# 8_GPS.net
KiCad netlist of a schematic drawn in Altium Designer
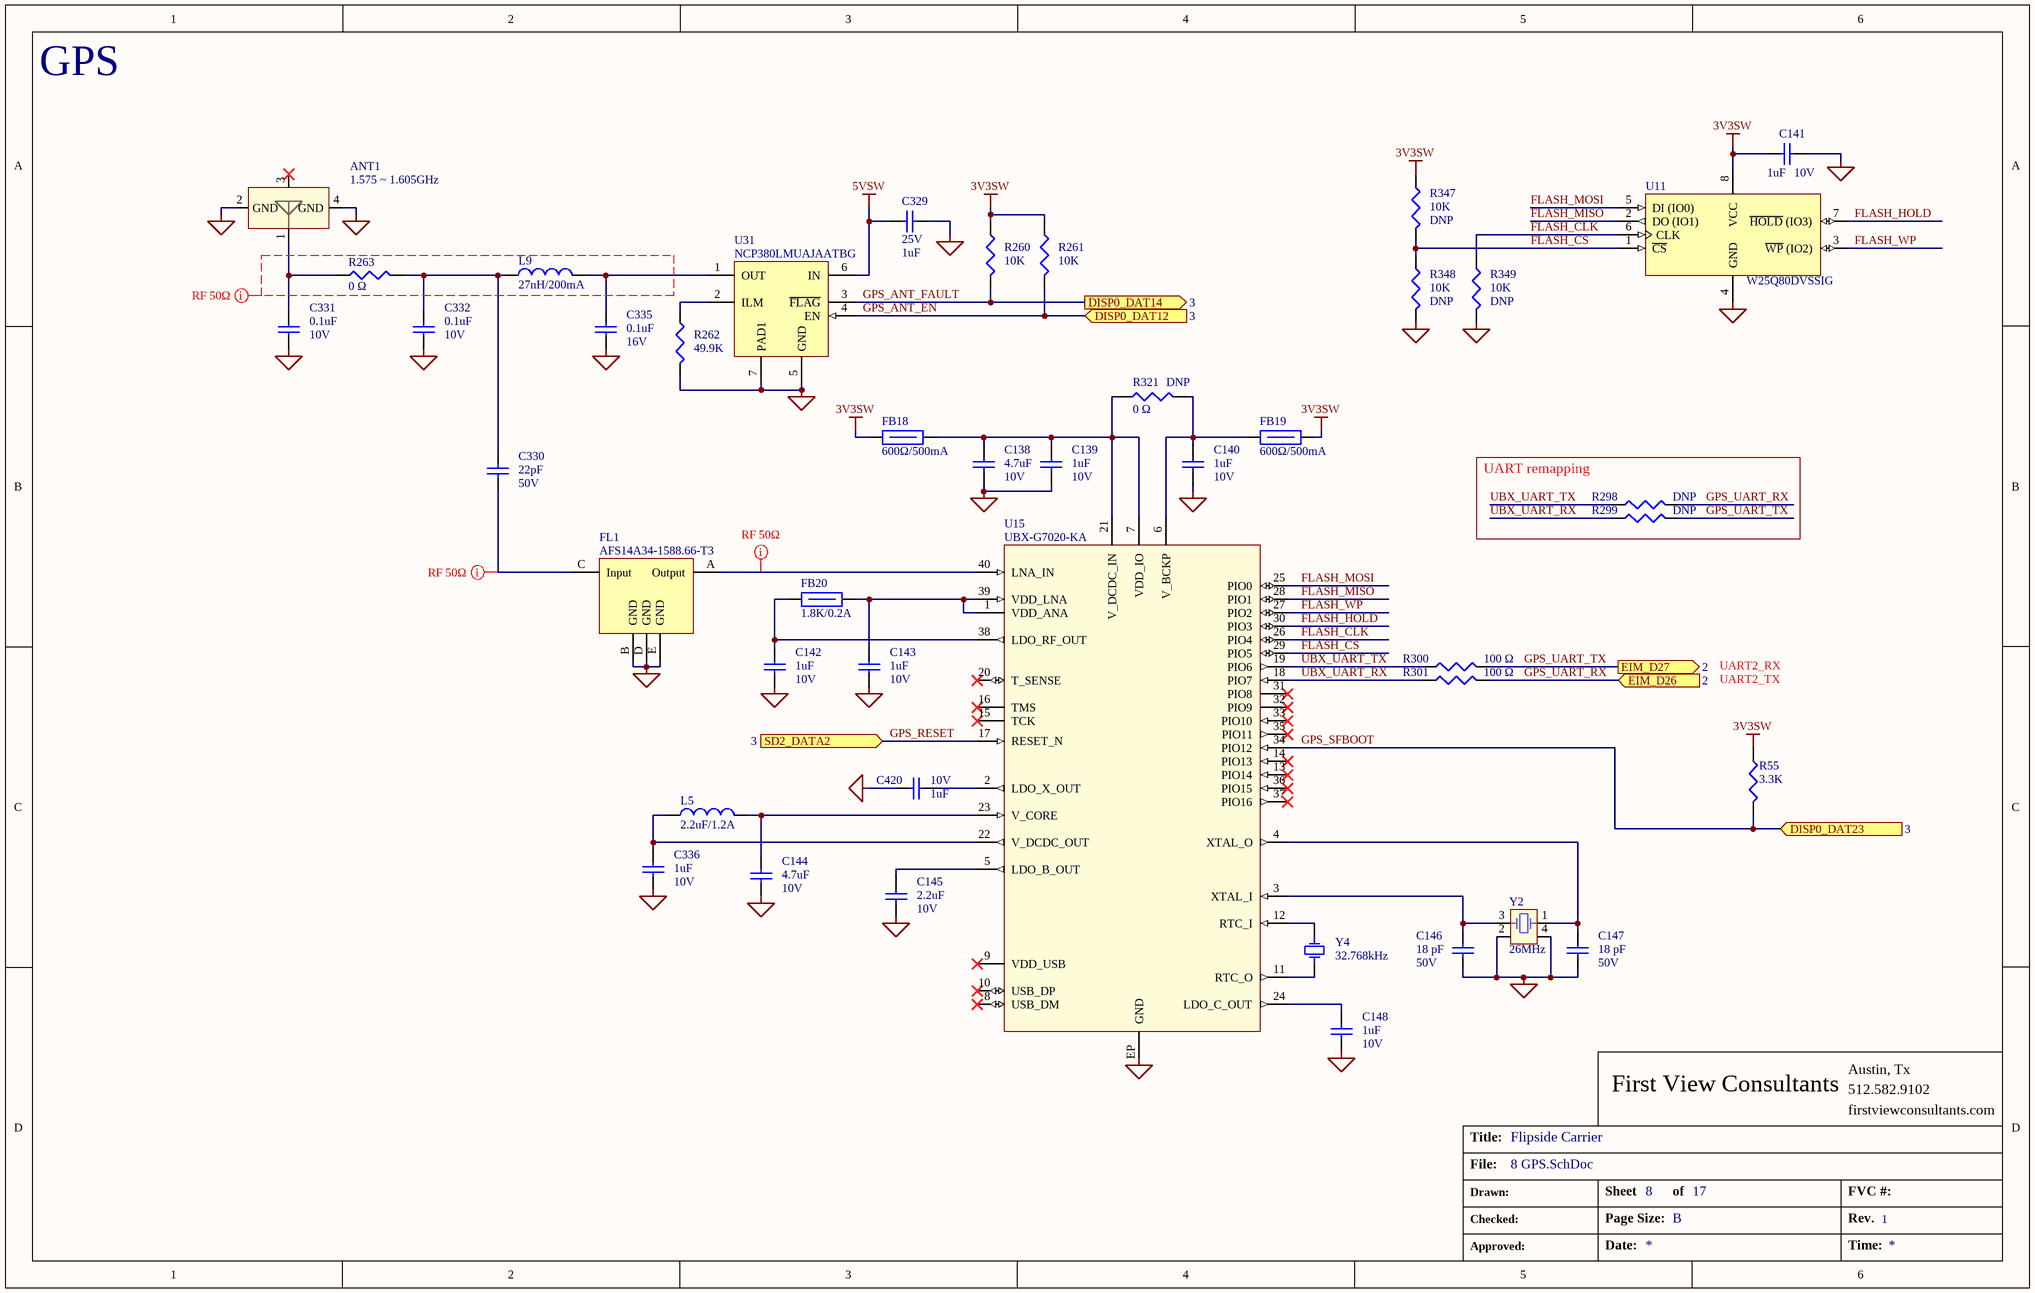
[diagram p0: 8 GPS.SchDoc]

(export (version "E")
  (design (tool "Eeschema 10.0.6"))
  (components
    (comp (ref "ANT1")
      (value "1.575 ~ 1.605GHz")
      (footprint "ANT_1575AT54A0010E")
      (description "Antenna, GPS GLONASS, SMD")
      (fields
        (field (name "MANUFACTURER") "Johanson Technology, Inc.")
        (field (name "Comment") "1575AT54A0010E")
      )
      (libsource (lib "Firstview") (part "1575AT54A0010E"))
    )
    (comp (ref "C138")
      (value "4.7uF")
      (footprint "CAP_0402")
      (description "Cap, Cer, 4.7uF, 10V, 10%, X5R, 0603")
      (fields
        (field (name "TOLERANCE") "±10%")
        (field (name "VOLTAGE") "10V")
        (field (name "MANUFACTURER") "Taiyo Yuden")
      )
      (libsource (lib "Firstview") (part "Cap 4.7uF 10V 0603"))
    )
    (comp (ref "C139")
      (value "1uF")
      (footprint "CAP_0402")
      (description "Cap, Cer, 1uF, 10V, ±10%, X5R, 0402")
      (fields
        (field (name "VOLTAGE") "10V")
        (field (name "MANUFACTURER") "Yageo")
        (field (name "Comment") "Cap 1uF 10V 0402")
      )
      (libsource (lib "Firstview") (part "Cap 1uF 10V 0402"))
    )
    (comp (ref "C140")
      (value "1uF")
      (footprint "CAP_0402")
      (description "Cap, Cer, 1uF, 10V, ±10%, X5R, 0402")
      (fields
        (field (name "VOLTAGE") "10V")
        (field (name "MANUFACTURER") "Yageo")
        (field (name "Comment") "Cap 1uF 10V 0402")
      )
      (libsource (lib "Firstview") (part "Cap 1uF 10V 0402"))
    )
    (comp (ref "C141")
      (value "1uF")
      (footprint "CAP_0402")
      (description "Cap, Cer, 1uF, 10V, ±10%, X5R, 0402")
      (fields
        (field (name "VOLTAGE") "10V")
        (field (name "MANUFACTURER") "Yageo")
        (field (name "Comment") "Cap 1uF 10V 0402")
      )
      (libsource (lib "Firstview") (part "Cap 1uF 10V 0402"))
    )
    (comp (ref "C142")
      (value "1uF")
      (footprint "CAP_0402")
      (description "Cap, Cer, 1uF, 10V, ±10%, X5R, 0402")
      (fields
        (field (name "VOLTAGE") "10V")
        (field (name "MANUFACTURER") "Yageo")
        (field (name "Comment") "Cap 1uF 10V 0402")
      )
      (libsource (lib "Firstview") (part "Cap 1uF 10V 0402"))
    )
    (comp (ref "C143")
      (value "1uF")
      (footprint "CAP_0402")
      (description "Cap, Cer, 1uF, 10V, ±10%, X5R, 0402")
      (fields
        (field (name "VOLTAGE") "10V")
        (field (name "MANUFACTURER") "Yageo")
        (field (name "Comment") "Cap 1uF 10V 0402")
      )
      (libsource (lib "Firstview") (part "Cap 1uF 10V 0402"))
    )
    (comp (ref "C144")
      (value "4.7uF")
      (footprint "CAP_0402")
      (description "Cap, Cer, 4.7uF, 10V, 10%, X5R, 0603")
      (fields
        (field (name "TOLERANCE") "±10%")
        (field (name "VOLTAGE") "10V")
        (field (name "MANUFACTURER") "Taiyo Yuden")
      )
      (libsource (lib "Firstview") (part "Cap 4.7uF 10V 0603"))
    )
    (comp (ref "C145")
      (value "2.2uF")
      (footprint "CAP_0402")
      (description "Cap, Cer, 2.2uF, 10V, 10%, X5R, 0402")
      (fields
        (field (name "VOLTAGE") "10V")
        (field (name "MANUFACTURER") "Kemet")
        (field (name "Comment") "Cap 2.2uF 10V 0402")
      )
      (libsource (lib "Firstview") (part "Cap 2.2uF 10V 0402"))
    )
    (comp (ref "C146")
      (value "18 pF")
      (footprint "CAP_0402")
      (description "Cap, Cer, 18pF, 50V, 5%, C0G, 0402")
      (fields
        (field (name "MANUFACTURER") "TDK Corporation")
        (field (name "VOLTAGE") "50V")
        (field (name "Comment") "Cap 18pF 50V 0402")
      )
      (libsource (lib "Firstview") (part "Cap 18pF 50V 0402"))
    )
    (comp (ref "C147")
      (value "18 pF")
      (footprint "CAP_0402")
      (description "Cap, Cer, 18pF, 50V, 5%, C0G, 0402")
      (fields
        (field (name "MANUFACTURER") "TDK Corporation")
        (field (name "VOLTAGE") "50V")
        (field (name "Comment") "Cap 18pF 50V 0402")
      )
      (libsource (lib "Firstview") (part "Cap 18pF 50V 0402"))
    )
    (comp (ref "C148")
      (value "1uF")
      (footprint "CAP_0402")
      (description "Cap, Cer, 1uF, 10V, ±10%, X5R, 0402")
      (fields
        (field (name "VOLTAGE") "10V")
        (field (name "MANUFACTURER") "Yageo")
        (field (name "Comment") "Cap 1uF 10V 0402")
      )
      (libsource (lib "Firstview") (part "Cap 1uF 10V 0402"))
    )
    (comp (ref "C329")
      (value "1uF")
      (footprint "CAP_0402")
      (description "Cap, Cer, 1uF, 25V, 10%, X5R, 0402")
      (fields
        (field (name "MANUFACTURER") "Taiyo Yuden")
        (field (name "VOLTAGE") "25V")
        (field (name "Comment") "Cap 1uF 25V 0402")
      )
      (libsource (lib "Firstview") (part "Cap 1uF 25V 0402"))
    )
    (comp (ref "C330")
      (value "22pF")
      (footprint "CAP_0402")
      (description "Cap, Cer, 22pF, 50V, 5%, C0G/NPO, 0402")
      (fields
        (field (name "MANUFACTURER") "Yageo")
        (field (name "VOLTAGE") "50V")
        (field (name "Comment") "Cap 22pF 50V 0402")
      )
      (libsource (lib "Firstview") (part "Cap 22pF 50V 0402"))
    )
    (comp (ref "C331")
      (value "0.1uF")
      (footprint "CAP_0402")
      (description "Cap, Cer, 0.1uF, 10V, 10%, X5R, 0402")
      (fields
        (field (name "TOLERANCE") "±10%")
        (field (name "MANUFACTURER") "Murata Electronics North America")
        (field (name "VOLTAGE") "10V")
      )
      (libsource (lib "Firstview") (part "Cap 0.1uF 10V 0402"))
    )
    (comp (ref "C332")
      (value "0.1uF")
      (footprint "CAP_0402")
      (description "Cap, Cer, 0.1uF, 10V, 10%, X5R, 0402")
      (fields
        (field (name "TOLERANCE") "±10%")
        (field (name "MANUFACTURER") "Murata Electronics North America")
        (field (name "VOLTAGE") "10V")
      )
      (libsource (lib "Firstview") (part "Cap 0.1uF 10V 0402"))
    )
    (comp (ref "C335")
      (value "0.1uF")
      (footprint "CAP_0402")
      (description "Cap, Cer, 0.1uF, 16V, 10%, X7R, 0402")
      (fields
        (field (name "TOLERANCE") "±10%")
        (field (name "MANUFACTURER") "Murata Electronics North America")
        (field (name "VOLTAGE") "16V")
      )
      (libsource (lib "Firstview") (part "Cap 0.1uF 16V 0402"))
    )
    (comp (ref "C336")
      (value "1uF")
      (footprint "CAP_0402")
      (description "Cap, Cer, 1uF, 10V, ±10%, X5R, 0402")
      (fields
        (field (name "VOLTAGE") "10V")
        (field (name "MANUFACTURER") "Yageo")
        (field (name "Comment") "Cap 1uF 10V 0402")
      )
      (libsource (lib "Firstview") (part "Cap 1uF 10V 0402"))
    )
    (comp (ref "C420")
      (value "1uF")
      (footprint "CAP_0402")
      (description "Cap, Cer, 1uF, 10V, ±10%, X5R, 0402")
      (fields
        (field (name "VOLTAGE") "10V")
        (field (name "MANUFACTURER") "Yageo")
        (field (name "Comment") "Cap 1uF 10V 0402")
      )
      (libsource (lib "Firstview") (part "Cap 1uF 10V 0402"))
    )
    (comp (ref "FB18")
      (value "600Ω/500mA")
      (footprint "IND_0603")
      (description "Ind, Ferrite Bead, 600R, 350mOhm, 0.5A, 0603")
      (fields
        (field (name "MANUFACTURER") "Murata Electronics North America")
        (field (name "Comment") "BLM18EG601SN1D")
      )
      (libsource (lib "Firstview") (part "BLM18EG601SN1D"))
    )
    (comp (ref "FB19")
      (value "600Ω/500mA")
      (footprint "IND_0603")
      (description "Ind, Ferrite Bead, 600R, 350mOhm, 0.5A, 0603")
      (fields
        (field (name "MANUFACTURER") "Murata Electronics North America")
        (field (name "Comment") "BLM18EG601SN1D")
      )
      (libsource (lib "Firstview") (part "BLM18EG601SN1D"))
    )
    (comp (ref "FB20")
      (value "1.8K/0.2A")
      (footprint "IND_0402")
      (description "Ind, Ferrite Bead, 1.8K, 2.2Ohm, 0.2A, 0402")
      (fields
        (field (name "MANUFACTURER") "Murata Electronics North America")
        (field (name "Comment") "BLM15HD182SN1")
      )
      (libsource (lib "Firstview") (part "BLM15HD182SN1"))
    )
    (comp (ref "FL1")
      (value "AFS14A34-1588.66-T3")
      (footprint "SMD(1.4x1.1)_AFS14A34-1588.66-T3")
      (description "Filter, SAW, 1.58866GHz, SMD")
      (fields (field (name "MANUFACTURER") "Abracon"))
      (libsource (lib "Firstview") (part "AFS14A34-1588.66-T3"))
    )
    (comp (ref "L5")
      (value "2.2uF/1.2A")
      (footprint "IND_0806")
      (description "Ind, Power, 2.2uH, 1.2A, 110 mOhm, 0806")
      (fields
        (field (name "TOLERANCE") "25%")
        (field (name "MANUFACTURER") "Murata Electronics North America")
      )
      (libsource (lib "Firstview") (part "LQM2MPN2R2NG0L"))
    )
    (comp (ref "L9")
      (value "27nH/200mA")
      (footprint "IND_0402")
      (description "Ind, RF, 27nH, 0.2A, 0402")
      (fields (field (name "TOLERANCE") "5%") (field (name "MANUFACTURER") "Johanson Technology Inc"))
      (libsource (lib "Firstview") (part "L-07C27NJV6T"))
    )
    (comp (ref "R55")
      (value "3.3K")
      (footprint "RES_0402")
      (description "Res, 3.3K, 0.063W, 1%, 0402")
      (fields (field (name "MANUFACTURER") "Rohm Semiconductor") (field (name "Comment") "Res 3.3K 0.063W"))
      (libsource (lib "Firstview") (part "Res 3.3K 0.063W"))
    )
    (comp (ref "R260")
      (value "10K")
      (footprint "RES_0402")
      (description "Res, 10K, 1/16W, 1%, 0402")
      (fields (field (name "MANUFACTURER") "Yageo") (field (name "Comment") "Res 10K 0.063W"))
      (libsource (lib "Firstview") (part "Res 10K 0.063W"))
    )
    (comp (ref "R261")
      (value "10K")
      (footprint "RES_0402")
      (description "Res, 10K, 1/16W, 1%, 0402")
      (fields (field (name "MANUFACTURER") "Yageo") (field (name "Comment") "Res 10K 0.063W"))
      (libsource (lib "Firstview") (part "Res 10K 0.063W"))
    )
    (comp (ref "R262")
      (value "49.9K")
      (footprint "RES_0402")
      (description "Res, 49.9K, 0.063W, 1%, 0402")
      (fields (field (name "MANUFACTURER") "Rohm Semiconductor") (field (name "Comment") "Res 49.9K 0.063W"))
      (libsource (lib "Firstview") (part "Res 49.9K 0.063W"))
    )
    (comp (ref "R263")
      (value "0 Ω")
      (footprint "RES_0402")
      (description "Res, 0 ohm, 1/16W, 0402")
      (fields (field (name "MANUFACTURER") "Vishay Dale") (field (name "Comment") "Res 0 ohm 0.1W"))
      (libsource (lib "Firstview") (part "Res 0 ohm 0.1W"))
    )
    (comp (ref "R298")
      (value "Res 0 ohm 0.1W DNP")
      (footprint "RES_0402")
      (description "Res, 0 ohm, 1/16W, 0402")
      (fields (field (name "MANUFACTURER") "Vishay Dale") (field (name "DNP") "DNP"))
      (libsource (lib "Firstview") (part "Res 0 ohm 0.1W DNP"))
    )
    (comp (ref "R299")
      (value "Res 0 ohm 0.1W DNP")
      (footprint "RES_0402")
      (description "Res, 0 ohm, 1/16W, 0402")
      (fields (field (name "MANUFACTURER") "Vishay Dale") (field (name "DNP") "DNP"))
      (libsource (lib "Firstview") (part "Res 0 ohm 0.1W DNP"))
    )
    (comp (ref "R300")
      (value "100 Ω")
      (footprint "RES_0402")
      (description "Res, 100R, 0.063W, 1%, 0402")
      (fields
        (field (name "MANUFACTURER") "Murata Electronics North America")
        (field (name "Comment") "Res 100R 0.063W")
      )
      (libsource (lib "Firstview") (part "Res 100R 0.063W"))
    )
    (comp (ref "R301")
      (value "100 Ω")
      (footprint "RES_0402")
      (description "Res, 100R, 0.063W, 1%, 0402")
      (fields
        (field (name "MANUFACTURER") "Murata Electronics North America")
        (field (name "Comment") "Res 100R 0.063W")
      )
      (libsource (lib "Firstview") (part "Res 100R 0.063W"))
    )
    (comp (ref "R321")
      (value "0 Ω")
      (footprint "RES_0402")
      (description "Res, 0 ohm, 1/16W, 0402")
      (fields
        (field (name "DNP") "DNP")
        (field (name "MANUFACTURER") "Vishay Dale")
        (field (name "Comment") "Res 0 ohm 0.1W")
      )
      (libsource (lib "Firstview") (part "Res 0 ohm 0.1W"))
    )
    (comp (ref "R347")
      (value "10K")
      (footprint "RES_0402")
      (description "Res, 10K, 1/16W, 1%, 0402")
      (fields
        (field (name "DNP") "DNP")
        (field (name "MANUFACTURER") "Yageo")
        (field (name "Comment") "Res 10K 0.063W")
      )
      (libsource (lib "Firstview") (part "Res 10K 0.063W"))
    )
    (comp (ref "R348")
      (value "10K")
      (footprint "RES_0402")
      (description "Res, 10K, 1/16W, 1%, 0402")
      (fields
        (field (name "DNP") "DNP")
        (field (name "MANUFACTURER") "Yageo")
        (field (name "Comment") "Res 10K 0.063W")
      )
      (libsource (lib "Firstview") (part "Res 10K 0.063W"))
    )
    (comp (ref "R349")
      (value "10K")
      (footprint "RES_0402")
      (description "Res, 10K, 1/16W, 1%, 0402")
      (fields
        (field (name "DNP") "DNP")
        (field (name "MANUFACTURER") "Yageo")
        (field (name "Comment") "Res 10K 0.063W")
      )
      (libsource (lib "Firstview") (part "Res 10K 0.063W"))
    )
    (comp (ref "U11")
      (value "W25Q80DVSSIG")
      (footprint "SOIC-8_W25Q80DVSSIG")
      (description "IC, Flash, SPI, 2.5/3/3.3V, 4M-bit, SOIC-8")
      (fields (field (name "MANUFACTURER") "Winbond"))
      (libsource (lib "Firstview") (part "W25Q80DVSSIG"))
    )
    (comp (ref "U15")
      (value "UBX-G7020-KA")
      (footprint "QFN-40_UBX-G7020-KA")
      (description "IC, GPS, QFN-40")
      (fields (field (name "MANUFACTURER") "U-Blox"))
      (libsource (lib "Firstview") (part "UBX-G7020-KA"))
    )
    (comp (ref "U31")
      (value "NCP380LMUAJAATBG")
      (footprint "UDFN-6_NCP380LMUAJAATBG")
      (description "IC, Power Switch, Adj., 2.1A, UDFN-6")
      (fields (field (name "MANUFACTURER") "ON Semiconductor"))
      (libsource (lib "Firstview") (part "NCP380LMUAJAATBG"))
    )
    (comp (ref "Y2")
      (value "26MHz")
      (footprint "DFN(3.2x2.5)_403I35D26M00000")
      (description "Clock, Crystal, 26MHz, 50ppm, 18pf, -40+85°C, SMD")
      (fields
        (field (name "MANUFACTURER") "CTS-Frequency Controls")
        (field (name "Comment") "403I35D26M00000")
      )
      (libsource (lib "Firstview") (part "403I35D26M00000"))
    )
    (comp (ref "Y4")
      (value "32.768kHz")
      (footprint "SMD(3.2x1.5)_SC32S-12.5PF20PPM")
      (description "Clock, Crystal, 32.768kHz, 20ppm, 12.5pf, SMD")
      (fields (field (name "MANUFACTURER") "Seiko Instruments") (field (name "Comment") "SC32S-12.5PF20PPM"))
      (libsource (lib "Firstview") (part "SC32S-12.5PF20PPM"))
    )
  )
  (nets
    (net (code "1") (name "/FLASH_CLK") (class "Default")
      (node (ref "R349") (pin "1") (pinfunction "1_1") (pintype "passive"))
      (node (ref "U11") (pin "6") (pinfunction "CLK_6") (pintype "input"))
      (node (ref "U15") (pin "26") (pinfunction "PIO4_26") (pintype "bidirectional"))
    )
    (net (code "2") (name "/FLASH_CS") (class "Default")
      (node (ref "R347") (pin "2") (pinfunction "2_2") (pintype "passive"))
      (node (ref "R348") (pin "1") (pinfunction "1_1") (pintype "passive"))
      (node (ref "U11") (pin "1") (pinfunction "~{CS}_1") (pintype "input"))
      (node (ref "U15") (pin "29") (pinfunction "PIO5_29") (pintype "bidirectional"))
    )
    (net (code "3") (name "/FLASH_HOLD") (class "Default")
      (node (ref "U11") (pin "7") (pinfunction "~{HOLD}_(IO3)_7") (pintype "bidirectional"))
      (node (ref "U15") (pin "30") (pinfunction "PIO3_30") (pintype "bidirectional"))
    )
    (net (code "4") (name "/FLASH_MISO") (class "Default")
      (node (ref "U11") (pin "2") (pinfunction "DO_(IO1)_2") (pintype "output"))
      (node (ref "U15") (pin "28") (pinfunction "PIO1_28") (pintype "bidirectional"))
    )
    (net (code "5") (name "/FLASH_MOSI") (class "Default")
      (node (ref "U11") (pin "5") (pinfunction "DI_(IO0)_5") (pintype "input"))
      (node (ref "U15") (pin "25") (pinfunction "PIO0_25") (pintype "bidirectional"))
    )
    (net (code "6") (name "/FLASH_WP") (class "Default")
      (node (ref "U11") (pin "3") (pinfunction "~{WP}_(IO2)_3") (pintype "bidirectional"))
      (node (ref "U15") (pin "27") (pinfunction "PIO2_27") (pintype "bidirectional"))
    )
    (net (code "7") (name "/GPS_ANT_EN") (class "Default")
      (node (ref "R261") (pin "2") (pinfunction "2_2") (pintype "passive"))
      (node (ref "U31") (pin "4") (pinfunction "EN_4") (pintype "input"))
    )
    (net (code "8") (name "/GPS_ANT_FAULT") (class "Default")
      (node (ref "R260") (pin "2") (pinfunction "2_2") (pintype "passive"))
      (node (ref "U31") (pin "3") (pinfunction "~{FLAG}_3") (pintype "tri_state"))
    )
    (net (code "9") (name "/GPS_RESET") (class "Default")
      (node (ref "U15") (pin "17") (pinfunction "RESET_N_17") (pintype "input"))
    )
    (net (code "10") (name "/GPS_SFBOOT") (class "Default")
      (node (ref "R55") (pin "2") (pinfunction "2_2") (pintype "passive"))
      (node (ref "U15") (pin "34") (pinfunction "PIO12_34") (pintype "input"))
    )
    (net (code "11") (name "/GPS_UART_RX") (class "Default")
      (node (ref "R298") (pin "2") (pinfunction "2_2") (pintype "passive"))
      (node (ref "R301") (pin "2") (pinfunction "2_2") (pintype "passive"))
    )
    (net (code "12") (name "/GPS_UART_TX") (class "Default")
      (node (ref "R299") (pin "2") (pinfunction "2_2") (pintype "passive"))
      (node (ref "R300") (pin "2") (pinfunction "2_2") (pintype "passive"))
    )
    (net (code "13") (name "/UBX_UART_RX") (class "Default")
      (node (ref "R299") (pin "1") (pinfunction "1_1") (pintype "passive"))
      (node (ref "R301") (pin "1") (pinfunction "1_1") (pintype "passive"))
      (node (ref "U15") (pin "18") (pinfunction "PIO7_18") (pintype "input"))
    )
    (net (code "14") (name "/UBX_UART_TX") (class "Default")
      (node (ref "R298") (pin "1") (pinfunction "1_1") (pintype "passive"))
      (node (ref "R300") (pin "1") (pinfunction "1_1") (pintype "passive"))
      (node (ref "U15") (pin "19") (pinfunction "PIO6_19") (pintype "output"))
    )
    (net (code "15") (name "3V3SW") (class "Default")
      (node (ref "C141") (pin "1") (pinfunction "1_1") (pintype "passive"))
      (node (ref "FB18") (pin "1") (pinfunction "1_1") (pintype "passive"))
      (node (ref "FB19") (pin "2") (pinfunction "2_2") (pintype "passive"))
      (node (ref "R260") (pin "1") (pinfunction "1_1") (pintype "passive"))
      (node (ref "R261") (pin "1") (pinfunction "1_1") (pintype "passive"))
      (node (ref "R347") (pin "1") (pinfunction "1_1") (pintype "passive"))
      (node (ref "R55") (pin "1") (pinfunction "1_1") (pintype "passive"))
      (node (ref "U11") (pin "8") (pinfunction "VCC_8") (pintype "power_in"))
    )
    (net (code "16") (name "5VSW") (class "Default")
      (node (ref "C329") (pin "1") (pinfunction "1_1") (pintype "passive"))
      (node (ref "U31") (pin "6") (pinfunction "IN_6") (pintype "power_in"))
    )
    (net (code "17") (name "GND") (class "Default")
      (node (ref "ANT1") (pin "2") (pinfunction "GND_2") (pintype "passive"))
      (node (ref "ANT1") (pin "4") (pinfunction "GND_4") (pintype "passive"))
      (node (ref "C138") (pin "2") (pinfunction "2_2") (pintype "passive"))
      (node (ref "C139") (pin "2") (pinfunction "2_2") (pintype "passive"))
      (node (ref "C140") (pin "2") (pinfunction "2_2") (pintype "passive"))
      (node (ref "C141") (pin "2") (pinfunction "2_2") (pintype "passive"))
      (node (ref "C142") (pin "2") (pinfunction "2_2") (pintype "passive"))
      (node (ref "C143") (pin "2") (pinfunction "2_2") (pintype "passive"))
      (node (ref "C144") (pin "2") (pinfunction "2_2") (pintype "passive"))
      (node (ref "C145") (pin "2") (pinfunction "2_2") (pintype "passive"))
      (node (ref "C146") (pin "1") (pinfunction "1_1") (pintype "passive"))
      (node (ref "C147") (pin "1") (pinfunction "1_1") (pintype "passive"))
      (node (ref "C148") (pin "2") (pinfunction "2_2") (pintype "passive"))
      (node (ref "C329") (pin "2") (pinfunction "2_2") (pintype "passive"))
      (node (ref "C331") (pin "1") (pinfunction "1_1") (pintype "passive"))
      (node (ref "C332") (pin "1") (pinfunction "1_1") (pintype "passive"))
      (node (ref "C335") (pin "2") (pinfunction "2_2") (pintype "passive"))
      (node (ref "C336") (pin "2") (pinfunction "2_2") (pintype "passive"))
      (node (ref "C420") (pin "2") (pinfunction "2_2") (pintype "passive"))
      (node (ref "FL1") (pin "B") (pinfunction "GND_B") (pintype "power_in"))
      (node (ref "FL1") (pin "D") (pinfunction "GND_D") (pintype "power_in"))
      (node (ref "FL1") (pin "E") (pinfunction "GND_E") (pintype "power_in"))
      (node (ref "R262") (pin "2") (pinfunction "2_2") (pintype "passive"))
      (node (ref "R348") (pin "2") (pinfunction "2_2") (pintype "passive"))
      (node (ref "R349") (pin "2") (pinfunction "2_2") (pintype "passive"))
      (node (ref "U11") (pin "4") (pinfunction "GND_4") (pintype "power_in"))
      (node (ref "U15") (pin "EP") (pinfunction "GND_EP") (pintype "power_in"))
      (node (ref "U31") (pin "5") (pinfunction "GND_5") (pintype "power_in"))
      (node (ref "U31") (pin "7") (pinfunction "PAD1_7") (pintype "power_in"))
      (node (ref "Y2") (pin "2") (pintype "passive"))
      (node (ref "Y2") (pin "4") (pintype "passive"))
    )
    (net (code "18") (name "Net-(ANT1-Pad1)") (class "Default")
      (node (ref "ANT1") (pin "1") (pinfunction "1_1") (pintype "passive"))
      (node (ref "C331") (pin "2") (pinfunction "2_2") (pintype "passive"))
      (node (ref "R263") (pin "1") (pinfunction "1_1") (pintype "passive"))
    )
    (net (code "19") (name "Net-(C330-Pad2)") (class "Default")
      (node (ref "C330") (pin "2") (pinfunction "2_2") (pintype "passive"))
      (node (ref "C332") (pin "2") (pinfunction "2_2") (pintype "passive"))
      (node (ref "L9") (pin "1") (pinfunction "1_1") (pintype "passive"))
      (node (ref "R263") (pin "2") (pinfunction "2_2") (pintype "passive"))
    )
    (net (code "20") (name "Net-(FL1-Input)") (class "Default")
      (node (ref "C330") (pin "1") (pinfunction "1_1") (pintype "passive"))
      (node (ref "FL1") (pin "C") (pinfunction "Input_C") (pintype "power_in"))
    )
    (net (code "21") (name "Net-(FL1-Output)") (class "Default")
      (node (ref "FL1") (pin "A") (pinfunction "Output_A") (pintype "power_in"))
      (node (ref "U15") (pin "40") (pinfunction "LNA_IN_40") (pintype "input"))
    )
    (net (code "22") (name "Net-(U15-LDO_B_OUT)") (class "Default")
      (node (ref "C145") (pin "1") (pinfunction "1_1") (pintype "passive"))
      (node (ref "U15") (pin "5") (pinfunction "LDO_B_OUT_5") (pintype "output"))
    )
    (net (code "23") (name "Net-(U15-LDO_C_OUT)") (class "Default")
      (node (ref "C148") (pin "1") (pinfunction "1_1") (pintype "passive"))
      (node (ref "U15") (pin "24") (pinfunction "LDO_C_OUT_24") (pintype "output"))
    )
    (net (code "24") (name "Net-(U15-LDO_RF_OUT)") (class "Default")
      (node (ref "C142") (pin "1") (pinfunction "1_1") (pintype "passive"))
      (node (ref "FB20") (pin "1") (pinfunction "1_1") (pintype "passive"))
      (node (ref "U15") (pin "38") (pinfunction "LDO_RF_OUT_38") (pintype "output"))
    )
    (net (code "25") (name "Net-(U15-LDO_X_OUT)") (class "Default")
      (node (ref "C420") (pin "1") (pinfunction "1_1") (pintype "passive"))
      (node (ref "U15") (pin "2") (pinfunction "LDO_X_OUT_2") (pintype "output"))
    )
    (net (code "26") (name "Net-(U15-RTC_I)") (class "Default")
      (node (ref "U15") (pin "12") (pinfunction "RTC_I_12") (pintype "input"))
      (node (ref "Y4") (pin "1") (pinfunction "OSC1_1") (pintype "passive"))
    )
    (net (code "27") (name "Net-(U15-RTC_O)") (class "Default")
      (node (ref "U15") (pin "11") (pinfunction "RTC_O_11") (pintype "output"))
      (node (ref "Y4") (pin "2") (pinfunction "OSC2_2") (pintype "passive"))
    )
    (net (code "28") (name "Net-(U15-VDD_ANA)") (class "Default")
      (node (ref "C143") (pin "1") (pinfunction "1_1") (pintype "passive"))
      (node (ref "FB20") (pin "2") (pinfunction "2_2") (pintype "passive"))
      (node (ref "U15") (pin "1") (pinfunction "VDD_ANA_1") (pintype "power_in"))
      (node (ref "U15") (pin "39") (pinfunction "VDD_LNA_39") (pintype "input"))
    )
    (net (code "29") (name "Net-(U15-VDD_IO)") (class "Default")
      (node (ref "C138") (pin "1") (pinfunction "1_1") (pintype "passive"))
      (node (ref "C139") (pin "1") (pinfunction "1_1") (pintype "passive"))
      (node (ref "FB18") (pin "2") (pinfunction "2_2") (pintype "passive"))
      (node (ref "R321") (pin "1") (pinfunction "1_1") (pintype "passive"))
      (node (ref "U15") (pin "21") (pinfunction "V_DCDC_IN_21") (pintype "power_in"))
      (node (ref "U15") (pin "7") (pinfunction "VDD_IO_7") (pintype "power_in"))
    )
    (net (code "30") (name "Net-(U15-V_BCKP)") (class "Default")
      (node (ref "C140") (pin "1") (pinfunction "1_1") (pintype "passive"))
      (node (ref "FB19") (pin "1") (pinfunction "1_1") (pintype "passive"))
      (node (ref "R321") (pin "2") (pinfunction "2_2") (pintype "passive"))
      (node (ref "U15") (pin "6") (pinfunction "V_BCKP_6") (pintype "power_in"))
    )
    (net (code "31") (name "Net-(U15-V_CORE)") (class "Default")
      (node (ref "C144") (pin "1") (pinfunction "1_1") (pintype "passive"))
      (node (ref "L5") (pin "2") (pinfunction "2_2") (pintype "passive"))
      (node (ref "U15") (pin "23") (pinfunction "V_CORE_23") (pintype "input"))
    )
    (net (code "32") (name "Net-(U15-V_DCDC_OUT)") (class "Default")
      (node (ref "C336") (pin "1") (pinfunction "1_1") (pintype "passive"))
      (node (ref "L5") (pin "1") (pinfunction "1_1") (pintype "passive"))
      (node (ref "U15") (pin "22") (pinfunction "V_DCDC_OUT_22") (pintype "output"))
    )
    (net (code "33") (name "Net-(U15-XTAL_I)") (class "Default")
      (node (ref "C146") (pin "2") (pinfunction "2_2") (pintype "passive"))
      (node (ref "U15") (pin "3") (pinfunction "XTAL_I_3") (pintype "input"))
      (node (ref "Y2") (pin "3") (pinfunction "OSC2_3") (pintype "passive"))
    )
    (net (code "34") (name "Net-(U15-XTAL_O)") (class "Default")
      (node (ref "C147") (pin "2") (pinfunction "2_2") (pintype "passive"))
      (node (ref "U15") (pin "4") (pinfunction "XTAL_O_4") (pintype "output"))
      (node (ref "Y2") (pin "1") (pinfunction "OSC1_1") (pintype "passive"))
    )
    (net (code "35") (name "Net-(U31-ILM)") (class "Default")
      (node (ref "R262") (pin "1") (pinfunction "1_1") (pintype "passive"))
      (node (ref "U31") (pin "2") (pinfunction "ILM_2") (pintype "passive"))
    )
    (net (code "36") (name "Net-(U31-OUT)") (class "Default")
      (node (ref "C335") (pin "1") (pinfunction "1_1") (pintype "passive"))
      (node (ref "L9") (pin "2") (pinfunction "2_2") (pintype "passive"))
      (node (ref "U31") (pin "1") (pinfunction "OUT_1") (pintype "power_in"))
    )
    (net (code "37") (name "unconnected-(ANT1-Pad3)") (class "Default")
      (node (ref "ANT1") (pin "3") (pinfunction "3_3") (pintype "passive+no_connect"))
    )
    (net (code "38") (name "unconnected-(U15-PIO8-Pad31)") (class "Default")
      (node (ref "U15") (pin "31") (pinfunction "PIO8_31") (pintype "passive+no_connect"))
    )
    (net (code "39") (name "unconnected-(U15-PIO9-Pad32)") (class "Default")
      (node (ref "U15") (pin "32") (pinfunction "PIO9_32") (pintype "passive+no_connect"))
    )
    (net (code "40") (name "unconnected-(U15-PIO10-Pad33)") (class "Default")
      (node (ref "U15") (pin "33") (pinfunction "PIO10_33") (pintype "input+no_connect"))
    )
    (net (code "41") (name "unconnected-(U15-PIO11-Pad35)") (class "Default")
      (node (ref "U15") (pin "35") (pinfunction "PIO11_35") (pintype "output+no_connect"))
    )
    (net (code "42") (name "unconnected-(U15-PIO13-Pad14)") (class "Default")
      (node (ref "U15") (pin "14") (pinfunction "PIO13_14") (pintype "input+no_connect"))
    )
    (net (code "43") (name "unconnected-(U15-PIO14-Pad13)") (class "Default")
      (node (ref "U15") (pin "13") (pinfunction "PIO14_13") (pintype "input+no_connect"))
    )
    (net (code "44") (name "unconnected-(U15-PIO15-Pad36)") (class "Default")
      (node (ref "U15") (pin "36") (pinfunction "PIO15_36") (pintype "input+no_connect"))
    )
    (net (code "45") (name "unconnected-(U15-PIO16-Pad37)") (class "Default")
      (node (ref "U15") (pin "37") (pinfunction "PIO16_37") (pintype "output+no_connect"))
    )
    (net (code "46") (name "unconnected-(U15-TCK-Pad15)") (class "Default")
      (node (ref "U15") (pin "15") (pinfunction "TCK_15") (pintype "passive+no_connect"))
    )
    (net (code "47") (name "unconnected-(U15-TMS-Pad16)") (class "Default")
      (node (ref "U15") (pin "16") (pinfunction "TMS_16") (pintype "passive+no_connect"))
    )
    (net (code "48") (name "unconnected-(U15-T_SENSE-Pad20)") (class "Default")
      (node (ref "U15") (pin "20") (pinfunction "T_SENSE_20") (pintype "bidirectional+no_connect"))
    )
    (net (code "49") (name "unconnected-(U15-USB_DM-Pad8)") (class "Default")
      (node (ref "U15") (pin "8") (pinfunction "USB_DM_8") (pintype "bidirectional+no_connect"))
    )
    (net (code "50") (name "unconnected-(U15-USB_DP-Pad10)") (class "Default")
      (node (ref "U15") (pin "10") (pinfunction "USB_DP_10") (pintype "bidirectional+no_connect"))
    )
    (net (code "51") (name "unconnected-(U15-VDD_USB-Pad9)") (class "Default")
      (node (ref "U15") (pin "9") (pinfunction "VDD_USB_9") (pintype "power_in+no_connect"))
    )
  )
)
